# NDSL.net
KiCad netlist of a schematic drawn in EasyEDA Pro
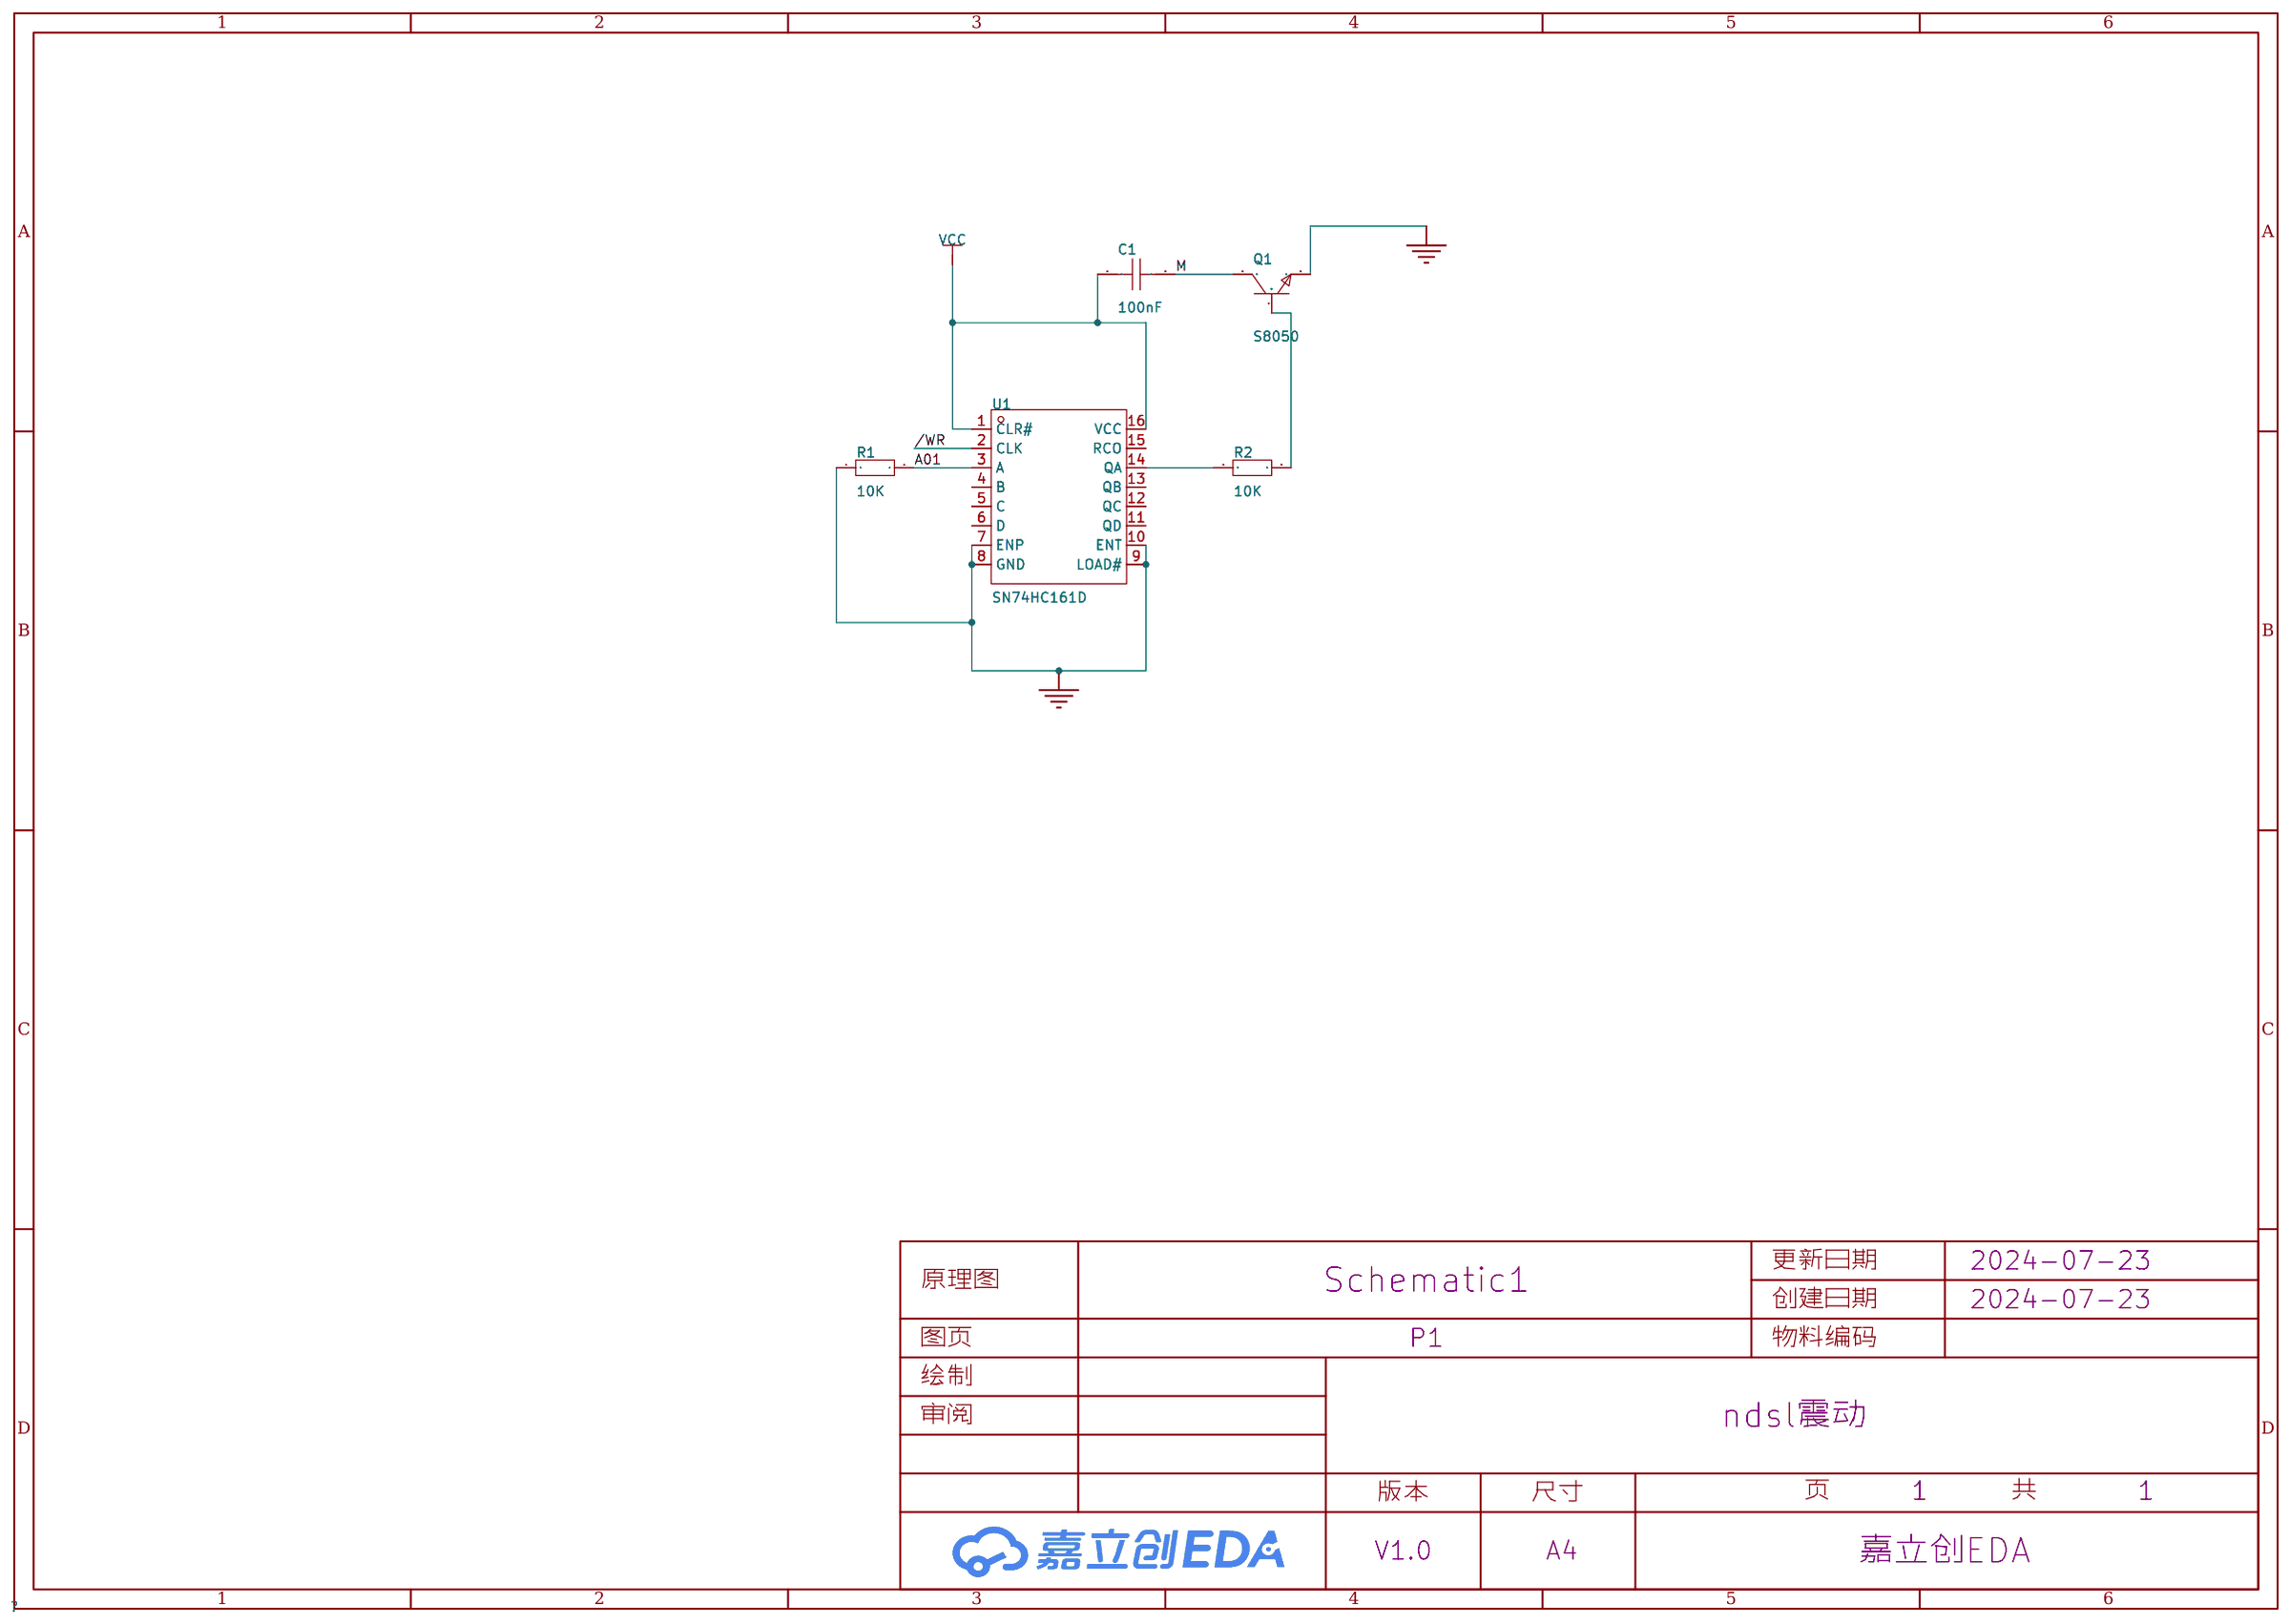
[diagram p0: schematic sheet]

(export (version "E")
  (design (tool "Eeschema 10.0.6"))
  (components
    (comp (ref "C1")
      (value "100nF")
      (footprint "easyedapro:C1206")
      (libsource (lib "easyedapro") (part "CapAcitance"))
    )
    (comp (ref "Q1")
      (value "S8050")
      (footprint "easyedapro:SOT-23-3_L2.9-W1.3-P1.90-LS2.3-BR")
      (description "晶体管类型:NPN;集电极电流(Ic):500mA;集射极击穿电压(Vceo):25V;功率(Pd):300mW;直流电流增益(hFE@Ic,Vce):120@50mA,1.0V;")
      (fields (field (name "Manufacturer") "宏迦橙"))
      (libsource (lib "easyedapro") (part "s8050_c20069125"))
    )
    (comp (ref "R1") (value "10K") (footprint "easyedapro:R1206") (libsource (lib "easyedapro") (part "电阻")))
    (comp (ref "R2") (value "10K") (footprint "easyedapro:R1206") (libsource (lib "easyedapro") (part "电阻")))
    (comp (ref "U1")
      (value "SN74HC161D")
      (footprint "easyedapro:SOIC-16_L9.9-W3.9-P1.27-LS6.0-BL")
      (description "工作电压:2V~6V;元件数:1;每个元件位数:4;触发器类型:正边沿;计数速率:36MHz;")
      (fields (field (name "Manufacturer") "TI(德州仪器)"))
      (libsource (lib "easyedapro") (part "SN74HC161D"))
    )
  )
  (nets
    (net (code "1") (name "/A01") (class "Default")
      (node (ref "R1") (pin "2") (pinfunction "2_2") (pintype "input"))
      (node (ref "U1") (pin "3") (pinfunction "A_3") (pintype "input"))
    )
    (net (code "2") (name "/M") (class "Default")
      (node (ref "C1") (pin "2") (pinfunction "2_2") (pintype "input"))
      (node (ref "Q1") (pin "3") (pinfunction "C_3") (pintype "input"))
    )
    (net (code "3") (name "/{slash}WR") (class "Default")
      (node (ref "U1") (pin "2") (pinfunction "CLK_2") (pintype "input"))
    )
    (net (code "4") (name "GND") (class "Default")
      (node (ref "Q1") (pin "2") (pinfunction "E_2") (pintype "input"))
      (node (ref "R1") (pin "1") (pinfunction "1_1") (pintype "input"))
      (node (ref "U1") (pin "10") (pinfunction "ENT_10") (pintype "input"))
      (node (ref "U1") (pin "7") (pinfunction "ENP_7") (pintype "input"))
      (node (ref "U1") (pin "8") (pinfunction "GND_8") (pintype "input"))
      (node (ref "U1") (pin "9") (pinfunction "LOAD#_9") (pintype "input"))
    )
    (net (code "5") (name "Net-(Q1-B)") (class "Default")
      (node (ref "Q1") (pin "1") (pinfunction "B_1") (pintype "input"))
      (node (ref "R2") (pin "2") (pinfunction "2_2") (pintype "input"))
    )
    (net (code "6") (name "Net-(U1-QA)") (class "Default")
      (node (ref "R2") (pin "1") (pinfunction "1_1") (pintype "input"))
      (node (ref "U1") (pin "14") (pinfunction "QA_14") (pintype "input"))
    )
    (net (code "7") (name "VCC") (class "Default")
      (node (ref "C1") (pin "1") (pinfunction "1_1") (pintype "input"))
      (node (ref "U1") (pin "1") (pinfunction "CLR#_1") (pintype "input"))
      (node (ref "U1") (pin "16") (pinfunction "VCC_16") (pintype "input"))
    )
    (net (code "8") (name "unconnected-(U1-B-Pad4)") (class "Default")
      (node (ref "U1") (pin "4") (pinfunction "B_4") (pintype "input"))
    )
    (net (code "9") (name "unconnected-(U1-C-Pad5)") (class "Default")
      (node (ref "U1") (pin "5") (pinfunction "C_5") (pintype "input"))
    )
    (net (code "10") (name "unconnected-(U1-D-Pad6)") (class "Default")
      (node (ref "U1") (pin "6") (pinfunction "D_6") (pintype "input"))
    )
    (net (code "11") (name "unconnected-(U1-QB-Pad13)") (class "Default")
      (node (ref "U1") (pin "13") (pinfunction "QB_13") (pintype "input"))
    )
    (net (code "12") (name "unconnected-(U1-QC-Pad12)") (class "Default")
      (node (ref "U1") (pin "12") (pinfunction "QC_12") (pintype "input"))
    )
    (net (code "13") (name "unconnected-(U1-QD-Pad11)") (class "Default")
      (node (ref "U1") (pin "11") (pinfunction "QD_11") (pintype "input"))
    )
    (net (code "14") (name "unconnected-(U1-RCO-Pad15)") (class "Default")
      (node (ref "U1") (pin "15") (pinfunction "RCO_15") (pintype "input"))
    )
  )
)
